# Power.net
KiCad netlist of a schematic drawn in Altium Designer
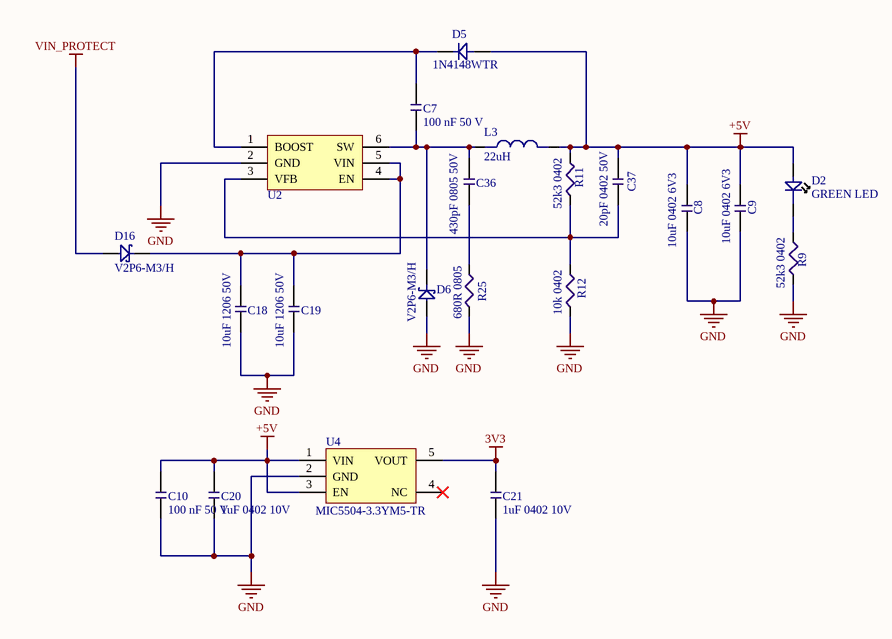
[diagram p0: Power.SchDoc]

(export (version "E")
  (design (tool "Eeschema 10.0.6"))
  (components
    (comp (ref "C7")
      (value "100 nF 50 V")
      (footprint "CAP_0402")
      (description "Multilayer Ceramic Capacitors MLCC - SMD/SMT .1uF 50Volts X7R +/-10% 0402 STD")
      (fields (field (name "TOLERANCE") "10%") (field (name "VOLTAGE") "50 V"))
      (libsource (lib "ON Development Vault") (part "Capacitor"))
    )
    (comp (ref "C8")
      (value "10uF 0402 6V3")
      (footprint "CAP_0402")
      (description "10uF 20% 0402 6V3 X6S")
      (fields (field (name "TOLERANCE") "20%") (field (name "VOLTAGE") "6V3"))
      (libsource (lib "ON Development Vault") (part "Capacitor"))
    )
    (comp (ref "C9")
      (value "10uF 0402 6V3")
      (footprint "CAP_0402")
      (description "10uF 20% 0402 6V3 X6S")
      (fields (field (name "TOLERANCE") "20%") (field (name "VOLTAGE") "6V3"))
      (libsource (lib "ON Development Vault") (part "Capacitor"))
    )
    (comp (ref "C10")
      (value "100 nF 50 V")
      (footprint "CAP_0402")
      (description "Multilayer Ceramic Capacitors MLCC - SMD/SMT .1uF 50Volts X7R +/-10% 0402 STD")
      (fields (field (name "TOLERANCE") "10%") (field (name "VOLTAGE") "50 V"))
      (libsource (lib "ON Development Vault") (part "Capacitor"))
    )
    (comp (ref "C18")
      (value "10uF 1206 50V")
      (footprint "CAP_1206")
      (description "10uF 1206 50V X5R 20%")
      (fields (field (name "TOLERANCE") "+/- 20%") (field (name "VOLTAGE") "50 V"))
      (libsource (lib "ON Development Vault") (part "Capacitor"))
    )
    (comp (ref "C19")
      (value "10uF 1206 50V")
      (footprint "CAP_1206")
      (description "10uF 1206 50V X5R 20%")
      (fields (field (name "TOLERANCE") "+/- 20%") (field (name "VOLTAGE") "50 V"))
      (libsource (lib "ON Development Vault") (part "Capacitor"))
    )
    (comp (ref "C20")
      (value "1uF 0402 10V")
      (footprint "CAP_0402")
      (description "1uF 0402 10V 10% X5R")
      (fields (field (name "TOLERANCE") "10%") (field (name "VOLTAGE") "10 V"))
      (libsource (lib "ON Development Vault") (part "Capacitor"))
    )
    (comp (ref "C21")
      (value "1uF 0402 10V")
      (footprint "CAP_0402")
      (description "1uF 0402 10V 10% X5R")
      (fields (field (name "TOLERANCE") "10%") (field (name "VOLTAGE") "10 V"))
      (libsource (lib "ON Development Vault") (part "Capacitor"))
    )
    (comp (ref "C36")
      (value "430pF 0805 50V")
      (footprint "CAP_0805")
      (description "CAP CER 430PF 50V C0G/NP0 0805")
      (fields (field (name "TOLERANCE") "5%") (field (name "VOLTAGE") "50V"))
      (libsource (lib "ON Development Vault") (part "Capacitor"))
    )
    (comp (ref "C37")
      (value "20pF 0402 50V")
      (footprint "CAP_0402")
      (description "20pF 0402 50V C0G 5%")
      (fields (field (name "TOLERANCE") "5%") (field (name "VOLTAGE") "50 V"))
      (libsource (lib "ON Development Vault") (part "Capacitor"))
    )
    (comp (ref "D2")
      (value "GREEN LED")
      (footprint "0402 LED")
      (description "0402 SMD LED")
      (fields (field (name "MFG. PART NUMBER") "LTST-C281KGKT"))
      (libsource (lib "ON Development Vault") (part "LED"))
    )
    (comp (ref "D5")
      (value "1N4148WTR")
      (footprint "SODFL371X135-2N")
      (description "DIODE GEN PURP 75V 250MA SOD123")
      (libsource (lib "ON Development Vault") (part "Diode"))
    )
    (comp (ref "D6")
      (value "V2P6-M3/H")
      (footprint "MicroSMP")
      (description "DIODE SCHOTTKY 60V 2A MICROSMP")
      (libsource (lib "ON Development Vault") (part "Schottky"))
    )
    (comp (ref "D16")
      (value "V2P6-M3/H")
      (footprint "MicroSMP")
      (description "DIODE SCHOTTKY 60V 2A MICROSMP")
      (libsource (lib "ON Development Vault") (part "Schottky"))
    )
    (comp (ref "L3")
      (value "22uH")
      (footprint "NR6028T220M")
      (description "FIXED IND 22UH 1.4A 175.5 MOHM")
      (fields (field (name "MFG. PART NUMBER") "NR6028T220M"))
      (libsource (lib "ON Development Vault") (part "Inductor"))
    )
    (comp (ref "R9")
      (value "52k3 0402")
      (footprint "RES_0402")
      (description "RES SMD 52.3K OHM 1% 1/16W 0402")
      (fields (field (name "POWER") "1/16 W") (field (name "TOLERANCE") "1 %"))
      (libsource (lib "ON Development Vault") (part "Resistor"))
    )
    (comp (ref "R11")
      (value "52k3 0402")
      (footprint "RES_0402")
      (description "RES SMD 52.3K OHM 1% 1/16W 0402")
      (fields (field (name "POWER") "1/16 W") (field (name "TOLERANCE") "1 %"))
      (libsource (lib "ON Development Vault") (part "Resistor"))
    )
    (comp (ref "R12")
      (value "10k 0402")
      (footprint "RES_0402")
      (description "RES SMD 10K OHM 1% 1/16W 0402")
      (fields (field (name "POWER") "1/16 W") (field (name "TOLERANCE") "1 %"))
      (libsource (lib "ON Development Vault") (part "Resistor"))
    )
    (comp (ref "R25")
      (value "680R 0805")
      (footprint "RES_0805")
      (description "RES SMD 680 OHM 1% 1/8W 0805")
      (fields (field (name "POWER") "1/8W") (field (name "TOLERANCE") "1%"))
      (libsource (lib "ON Development Vault") (part "Resistor"))
    )
    (comp (ref "U2")
      (value "MCP16331")
      (footprint "SOT95P280X145-6N")
      (description "High-Voltage Input Integrated Switch Step-Down Regulator")
      (libsource (lib "ON Development Vault") (part "MCP16331"))
    )
    (comp (ref "U4")
      (value "MIC5504-3.3YM5-TR")
      (footprint "SOT95P280X130-5N")
      (description "LDO Voltage Regulators Single 300mA")
      (libsource (lib "ON Development Vault") (part "MIC5504"))
    )
  )
  (nets
    (net (code "1") (name "+5V") (class "Default")
      (node (ref "C10") (pin "1") (pinfunction "1_1") (pintype "passive"))
      (node (ref "C20") (pin "2") (pinfunction "2_2") (pintype "passive"))
      (node (ref "C37") (pin "1") (pinfunction "1_1") (pintype "passive"))
      (node (ref "C8") (pin "2") (pinfunction "2_2") (pintype "passive"))
      (node (ref "C9") (pin "2") (pinfunction "2_2") (pintype "passive"))
      (node (ref "D2") (pin "1") (pinfunction "1_1") (pintype "passive"))
      (node (ref "D5") (pin "1") (pinfunction "1_1") (pintype "passive"))
      (node (ref "L3") (pin "2") (pinfunction "2_2") (pintype "passive"))
      (node (ref "R11") (pin "2") (pinfunction "2_2") (pintype "passive"))
      (node (ref "U4") (pin "1") (pinfunction "VIN_1") (pintype "passive"))
      (node (ref "U4") (pin "3") (pinfunction "EN_3") (pintype "passive"))
    )
    (net (code "2") (name "3V3") (class "Default")
      (node (ref "C21") (pin "2") (pinfunction "2_2") (pintype "passive"))
      (node (ref "U4") (pin "5") (pinfunction "VOUT_5") (pintype "passive"))
    )
    (net (code "3") (name "GND") (class "Default")
      (node (ref "C10") (pin "2") (pinfunction "2_2") (pintype "passive"))
      (node (ref "C18") (pin "1") (pinfunction "1_1") (pintype "passive"))
      (node (ref "C19") (pin "1") (pinfunction "1_1") (pintype "passive"))
      (node (ref "C20") (pin "1") (pinfunction "1_1") (pintype "passive"))
      (node (ref "C21") (pin "1") (pinfunction "1_1") (pintype "passive"))
      (node (ref "C8") (pin "1") (pinfunction "1_1") (pintype "passive"))
      (node (ref "C9") (pin "1") (pinfunction "1_1") (pintype "passive"))
      (node (ref "D6") (pin "1") (pinfunction "1_1") (pintype "passive"))
      (node (ref "R12") (pin "1") (pinfunction "1_1") (pintype "passive"))
      (node (ref "R25") (pin "1") (pinfunction "1_1") (pintype "passive"))
      (node (ref "R9") (pin "1") (pinfunction "1_1") (pintype "passive"))
      (node (ref "U2") (pin "2") (pinfunction "GND_2") (pintype "passive"))
      (node (ref "U4") (pin "2") (pinfunction "GND_2") (pintype "passive"))
    )
    (net (code "4") (name "Net-(C36-Pad2)") (class "Default")
      (node (ref "C36") (pin "2") (pinfunction "2_2") (pintype "passive"))
      (node (ref "R25") (pin "2") (pinfunction "2_2") (pintype "passive"))
    )
    (net (code "5") (name "Net-(D2-Pad2)") (class "Default")
      (node (ref "D2") (pin "2") (pinfunction "2_2") (pintype "passive"))
      (node (ref "R9") (pin "2") (pinfunction "2_2") (pintype "passive"))
    )
    (net (code "6") (name "Net-(U2-BOOST)") (class "Default")
      (node (ref "C7") (pin "1") (pinfunction "1_1") (pintype "passive"))
      (node (ref "D5") (pin "2") (pinfunction "2_2") (pintype "passive"))
      (node (ref "U2") (pin "1") (pinfunction "BOOST_1") (pintype "passive"))
    )
    (net (code "7") (name "Net-(U2-EN)") (class "Default")
      (node (ref "C18") (pin "2") (pinfunction "2_2") (pintype "passive"))
      (node (ref "C19") (pin "2") (pinfunction "2_2") (pintype "passive"))
      (node (ref "D16") (pin "2") (pinfunction "2_2") (pintype "passive"))
      (node (ref "U2") (pin "4") (pinfunction "EN_4") (pintype "passive"))
      (node (ref "U2") (pin "5") (pinfunction "VIN_5") (pintype "passive"))
    )
    (net (code "8") (name "Net-(U2-SW)") (class "Default")
      (node (ref "C36") (pin "1") (pinfunction "1_1") (pintype "passive"))
      (node (ref "C7") (pin "2") (pinfunction "2_2") (pintype "passive"))
      (node (ref "D6") (pin "2") (pinfunction "2_2") (pintype "passive"))
      (node (ref "L3") (pin "1") (pinfunction "1_1") (pintype "passive"))
      (node (ref "U2") (pin "6") (pinfunction "SW_6") (pintype "passive"))
    )
    (net (code "9") (name "Net-(U2-VFB)") (class "Default")
      (node (ref "C37") (pin "2") (pinfunction "2_2") (pintype "passive"))
      (node (ref "R11") (pin "1") (pinfunction "1_1") (pintype "passive"))
      (node (ref "R12") (pin "2") (pinfunction "2_2") (pintype "passive"))
      (node (ref "U2") (pin "3") (pinfunction "VFB_3") (pintype "passive"))
    )
    (net (code "10") (name "VIN_PROTECT") (class "Default")
      (node (ref "D16") (pin "1") (pinfunction "1_1") (pintype "passive"))
    )
    (net (code "11") (name "unconnected-(U4-NC-Pad4)") (class "Default")
      (node (ref "U4") (pin "4") (pinfunction "NC_4") (pintype "passive+no_connect"))
    )
  )
)
